# AinCHr2.net
KiCad netlist of a schematic drawn in Altium Designer
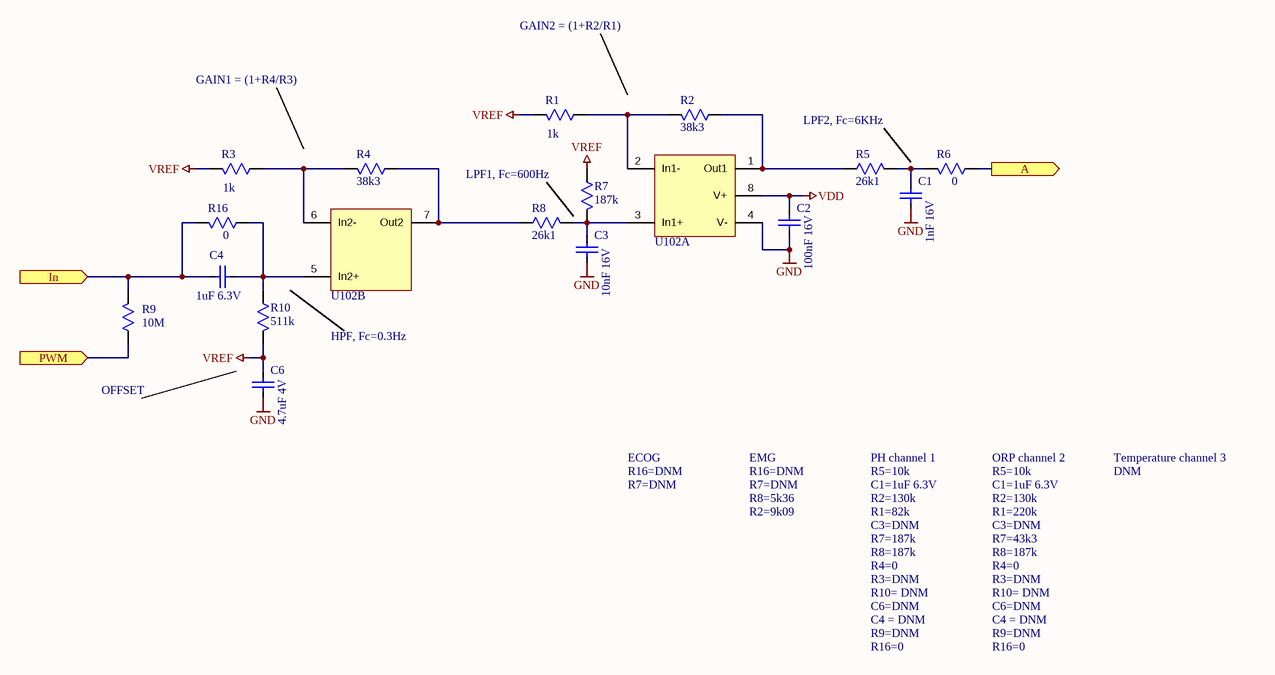
[diagram p0: AinCHr2.SchDoc]

(export (version "E")
  (design (tool "Eeschema 10.0.6"))
  (components
    (comp (ref "C1")
      (value "1nF 16V")
      (footprint "CAPC0603L")
      (description "Capacitor")
      (libsource (lib "ECOG") (part "Capacitor"))
    )
    (comp (ref "C2")
      (value "100nF 16V")
      (footprint "CAPC0603L")
      (description "Capacitor")
      (libsource (lib "ECOG") (part "Capacitor"))
    )
    (comp (ref "C3")
      (value "10nF 16V")
      (footprint "CAPC0603L")
      (description "Capacitor")
      (libsource (lib "ECOG") (part "Capacitor"))
    )
    (comp (ref "C4")
      (value "1uF 6.3V")
      (footprint "CAPC0603L")
      (description "Capacitor")
      (libsource (lib "ECOG") (part "Capacitor"))
    )
    (comp (ref "C6")
      (value "4.7uF 4V")
      (footprint "CAPC0603L")
      (description "Capacitor")
      (libsource (lib "ECOG") (part "Capacitor"))
    )
    (comp (ref "R1")
      (value "1k")
      (footprint "RESC0603L")
      (description "Resistor")
      (libsource (lib "ECOG") (part "Resistor"))
    )
    (comp (ref "R2")
      (value "38k3")
      (footprint "RESC0603L")
      (description "Resistor")
      (libsource (lib "ECOG") (part "Resistor"))
    )
    (comp (ref "R3")
      (value "1k")
      (footprint "RESC0603L")
      (description "Resistor")
      (libsource (lib "ECOG") (part "Resistor"))
    )
    (comp (ref "R4")
      (value "38k3")
      (footprint "RESC0603L")
      (description "Resistor")
      (libsource (lib "ECOG") (part "Resistor"))
    )
    (comp (ref "R5")
      (value "26k1")
      (footprint "RESC0603L")
      (description "Resistor")
      (libsource (lib "ECOG") (part "Resistor"))
    )
    (comp (ref "R6")
      (value "0")
      (footprint "RESC0603L")
      (description "Resistor")
      (libsource (lib "ECOG") (part "Resistor"))
    )
    (comp (ref "R7")
      (value "187k")
      (footprint "RESC0603L")
      (description "Resistor")
      (libsource (lib "ECOG") (part "Resistor"))
    )
    (comp (ref "R8")
      (value "26k1")
      (footprint "RESC0603L")
      (description "Resistor")
      (libsource (lib "ECOG") (part "Resistor"))
    )
    (comp (ref "R9")
      (value "10M")
      (footprint "RESC0603L")
      (description "Resistor")
      (libsource (lib "ECOG") (part "Resistor"))
    )
    (comp (ref "R10")
      (value "511k")
      (footprint "RESC0603L")
      (description "Resistor")
      (libsource (lib "ECOG") (part "Resistor"))
    )
    (comp (ref "R16")
      (value "0")
      (footprint "RESC0603L")
      (description "Resistor")
      (libsource (lib "ECOG") (part "Resistor"))
    )
    (comp (ref "U102")
      (value "LMX358IQ2T")
      (footprint "SON50P200X60_HS-9L")
      (description "Operational Amplifier for Cost-Sensitive Systems")
      (libsource (lib "ECOG") (part "LMX358"))
    )
  )
  (nets
    (net (code "1") (name "/A") (class "Default")
      (node (ref "R6") (pin "1") (pinfunction "1_1") (pintype "passive"))
    )
    (net (code "2") (name "/In") (class "Default")
      (node (ref "C4") (pin "1") (pinfunction "1_1") (pintype "passive"))
      (node (ref "R16") (pin "2") (pinfunction "2_2") (pintype "passive"))
      (node (ref "R9") (pin "2") (pinfunction "2_2") (pintype "passive"))
    )
    (net (code "3") (name "/PWM") (class "Default")
      (node (ref "R9") (pin "1") (pinfunction "1_1") (pintype "passive"))
    )
    (net (code "4") (name "GND") (class "Default")
      (node (ref "C1") (pin "2") (pinfunction "2_2") (pintype "passive"))
      (node (ref "C2") (pin "2") (pinfunction "2_2") (pintype "passive"))
      (node (ref "C3") (pin "2") (pinfunction "2_2") (pintype "passive"))
      (node (ref "C6") (pin "2") (pinfunction "2_2") (pintype "passive"))
      (node (ref "U102") (pin "4") (pinfunction "V-_4") (pintype "passive"))
    )
    (net (code "5") (name "Net-(C1-Pad1)") (class "Default")
      (node (ref "C1") (pin "1") (pinfunction "1_1") (pintype "passive"))
      (node (ref "R5") (pin "2") (pinfunction "2_2") (pintype "passive"))
      (node (ref "R6") (pin "2") (pinfunction "2_2") (pintype "passive"))
    )
    (net (code "6") (name "Net-(U102A-In1+)") (class "Default")
      (node (ref "C3") (pin "1") (pinfunction "1_1") (pintype "passive"))
      (node (ref "R7") (pin "2") (pinfunction "2_2") (pintype "passive"))
      (node (ref "R8") (pin "2") (pinfunction "2_2") (pintype "passive"))
      (node (ref "U102") (pin "3") (pinfunction "In1+_3") (pintype "passive"))
    )
    (net (code "7") (name "Net-(U102A-In1-)") (class "Default")
      (node (ref "R1") (pin "1") (pinfunction "1_1") (pintype "passive"))
      (node (ref "R2") (pin "2") (pinfunction "2_2") (pintype "passive"))
      (node (ref "U102") (pin "2") (pinfunction "In1-_2") (pintype "passive"))
    )
    (net (code "8") (name "Net-(U102A-Out1)") (class "Default")
      (node (ref "R2") (pin "1") (pinfunction "1_1") (pintype "passive"))
      (node (ref "R5") (pin "1") (pinfunction "1_1") (pintype "passive"))
      (node (ref "U102") (pin "1") (pinfunction "Out1_1") (pintype "passive"))
    )
    (net (code "9") (name "Net-(U102B-In2+)") (class "Default")
      (node (ref "C4") (pin "2") (pinfunction "2_2") (pintype "passive"))
      (node (ref "R10") (pin "1") (pinfunction "1_1") (pintype "passive"))
      (node (ref "R16") (pin "1") (pinfunction "1_1") (pintype "passive"))
      (node (ref "U102") (pin "5") (pinfunction "In2+_5") (pintype "passive"))
    )
    (net (code "10") (name "Net-(U102B-In2-)") (class "Default")
      (node (ref "R3") (pin "1") (pinfunction "1_1") (pintype "passive"))
      (node (ref "R4") (pin "2") (pinfunction "2_2") (pintype "passive"))
      (node (ref "U102") (pin "6") (pinfunction "In2-_6") (pintype "passive"))
    )
    (net (code "11") (name "Net-(U102B-Out2)") (class "Default")
      (node (ref "R4") (pin "1") (pinfunction "1_1") (pintype "passive"))
      (node (ref "R8") (pin "1") (pinfunction "1_1") (pintype "passive"))
      (node (ref "U102") (pin "7") (pinfunction "Out2_7") (pintype "passive"))
    )
    (net (code "12") (name "VDD") (class "Default")
      (node (ref "C2") (pin "1") (pinfunction "1_1") (pintype "passive"))
      (node (ref "U102") (pin "8") (pinfunction "V+_8") (pintype "passive"))
    )
    (net (code "13") (name "VREF") (class "Default")
      (node (ref "C6") (pin "1") (pinfunction "1_1") (pintype "passive"))
      (node (ref "R1") (pin "2") (pinfunction "2_2") (pintype "passive"))
      (node (ref "R10") (pin "2") (pinfunction "2_2") (pintype "passive"))
      (node (ref "R3") (pin "2") (pinfunction "2_2") (pintype "passive"))
      (node (ref "R7") (pin "1") (pinfunction "1_1") (pintype "passive"))
    )
  )
)
